# LED_Blue_Direct_BRIGHT.net
KiCad netlist of a schematic drawn in Altium Designer
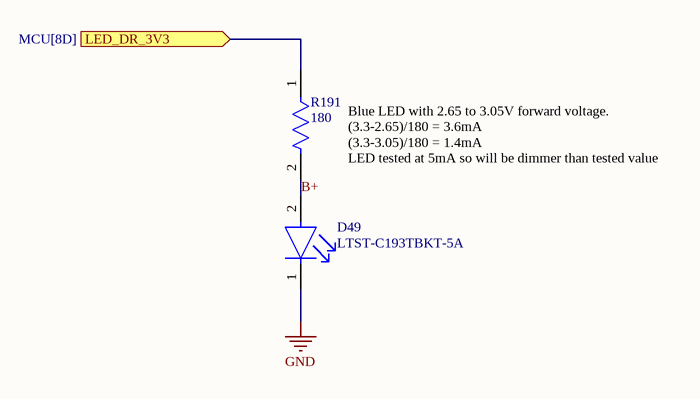
[diagram p0:  LED_Blue_Direct_BRIGHT.SchDoc]

(export (version "E")
  (design (tool "Eeschema 10.0.6"))
  (components
    (comp (ref "D49")
      (value "LTST-C193TBKT-5A")
      (footprint "FP-LTST-C193TBKT-5A-MFG")
      (description "LED blue 0603 wavelength 465~475nm light intensity 15mcd Front Mounting")
      (libsource (lib "HIL RIG FYP") (part "8706943c75ba83719d021d2fdc84c58"))
    )
    (comp (ref "R191")
      (value "180")
      (footprint "FP-RT0603-IPC_C")
      (description "Res Thin Film 0603 180 Ohm 0.5% 0.1W(1/10W) ±50ppm/C Pad SMD T/R")
      (fields (field (name "TOLERANCE") "0.5%") (field (name "Comment") "RT0603DRE07180RL"))
      (libsource (lib "HIL RIG FYP") (part "1029c3af85768c4190bb7ad29bc67b5"))
    )
  )
  (nets
    (net (code "1") (name "/B+") (class "Default")
      (node (ref "D49") (pin "2") (pinfunction "A_2") (pintype "passive"))
      (node (ref "R191") (pin "2") (pinfunction "2_2") (pintype "passive"))
    )
    (net (code "2") (name "/LED_DR_3V3") (class "Default")
      (node (ref "R191") (pin "1") (pinfunction "1_1") (pintype "passive"))
    )
    (net (code "3") (name "GND") (class "Default")
      (node (ref "D49") (pin "1") (pinfunction "C_1") (pintype "passive"))
    )
  )
)
